# SDB628_Evaluation_board.net
KiCad netlist of a schematic drawn in EasyEDA Pro
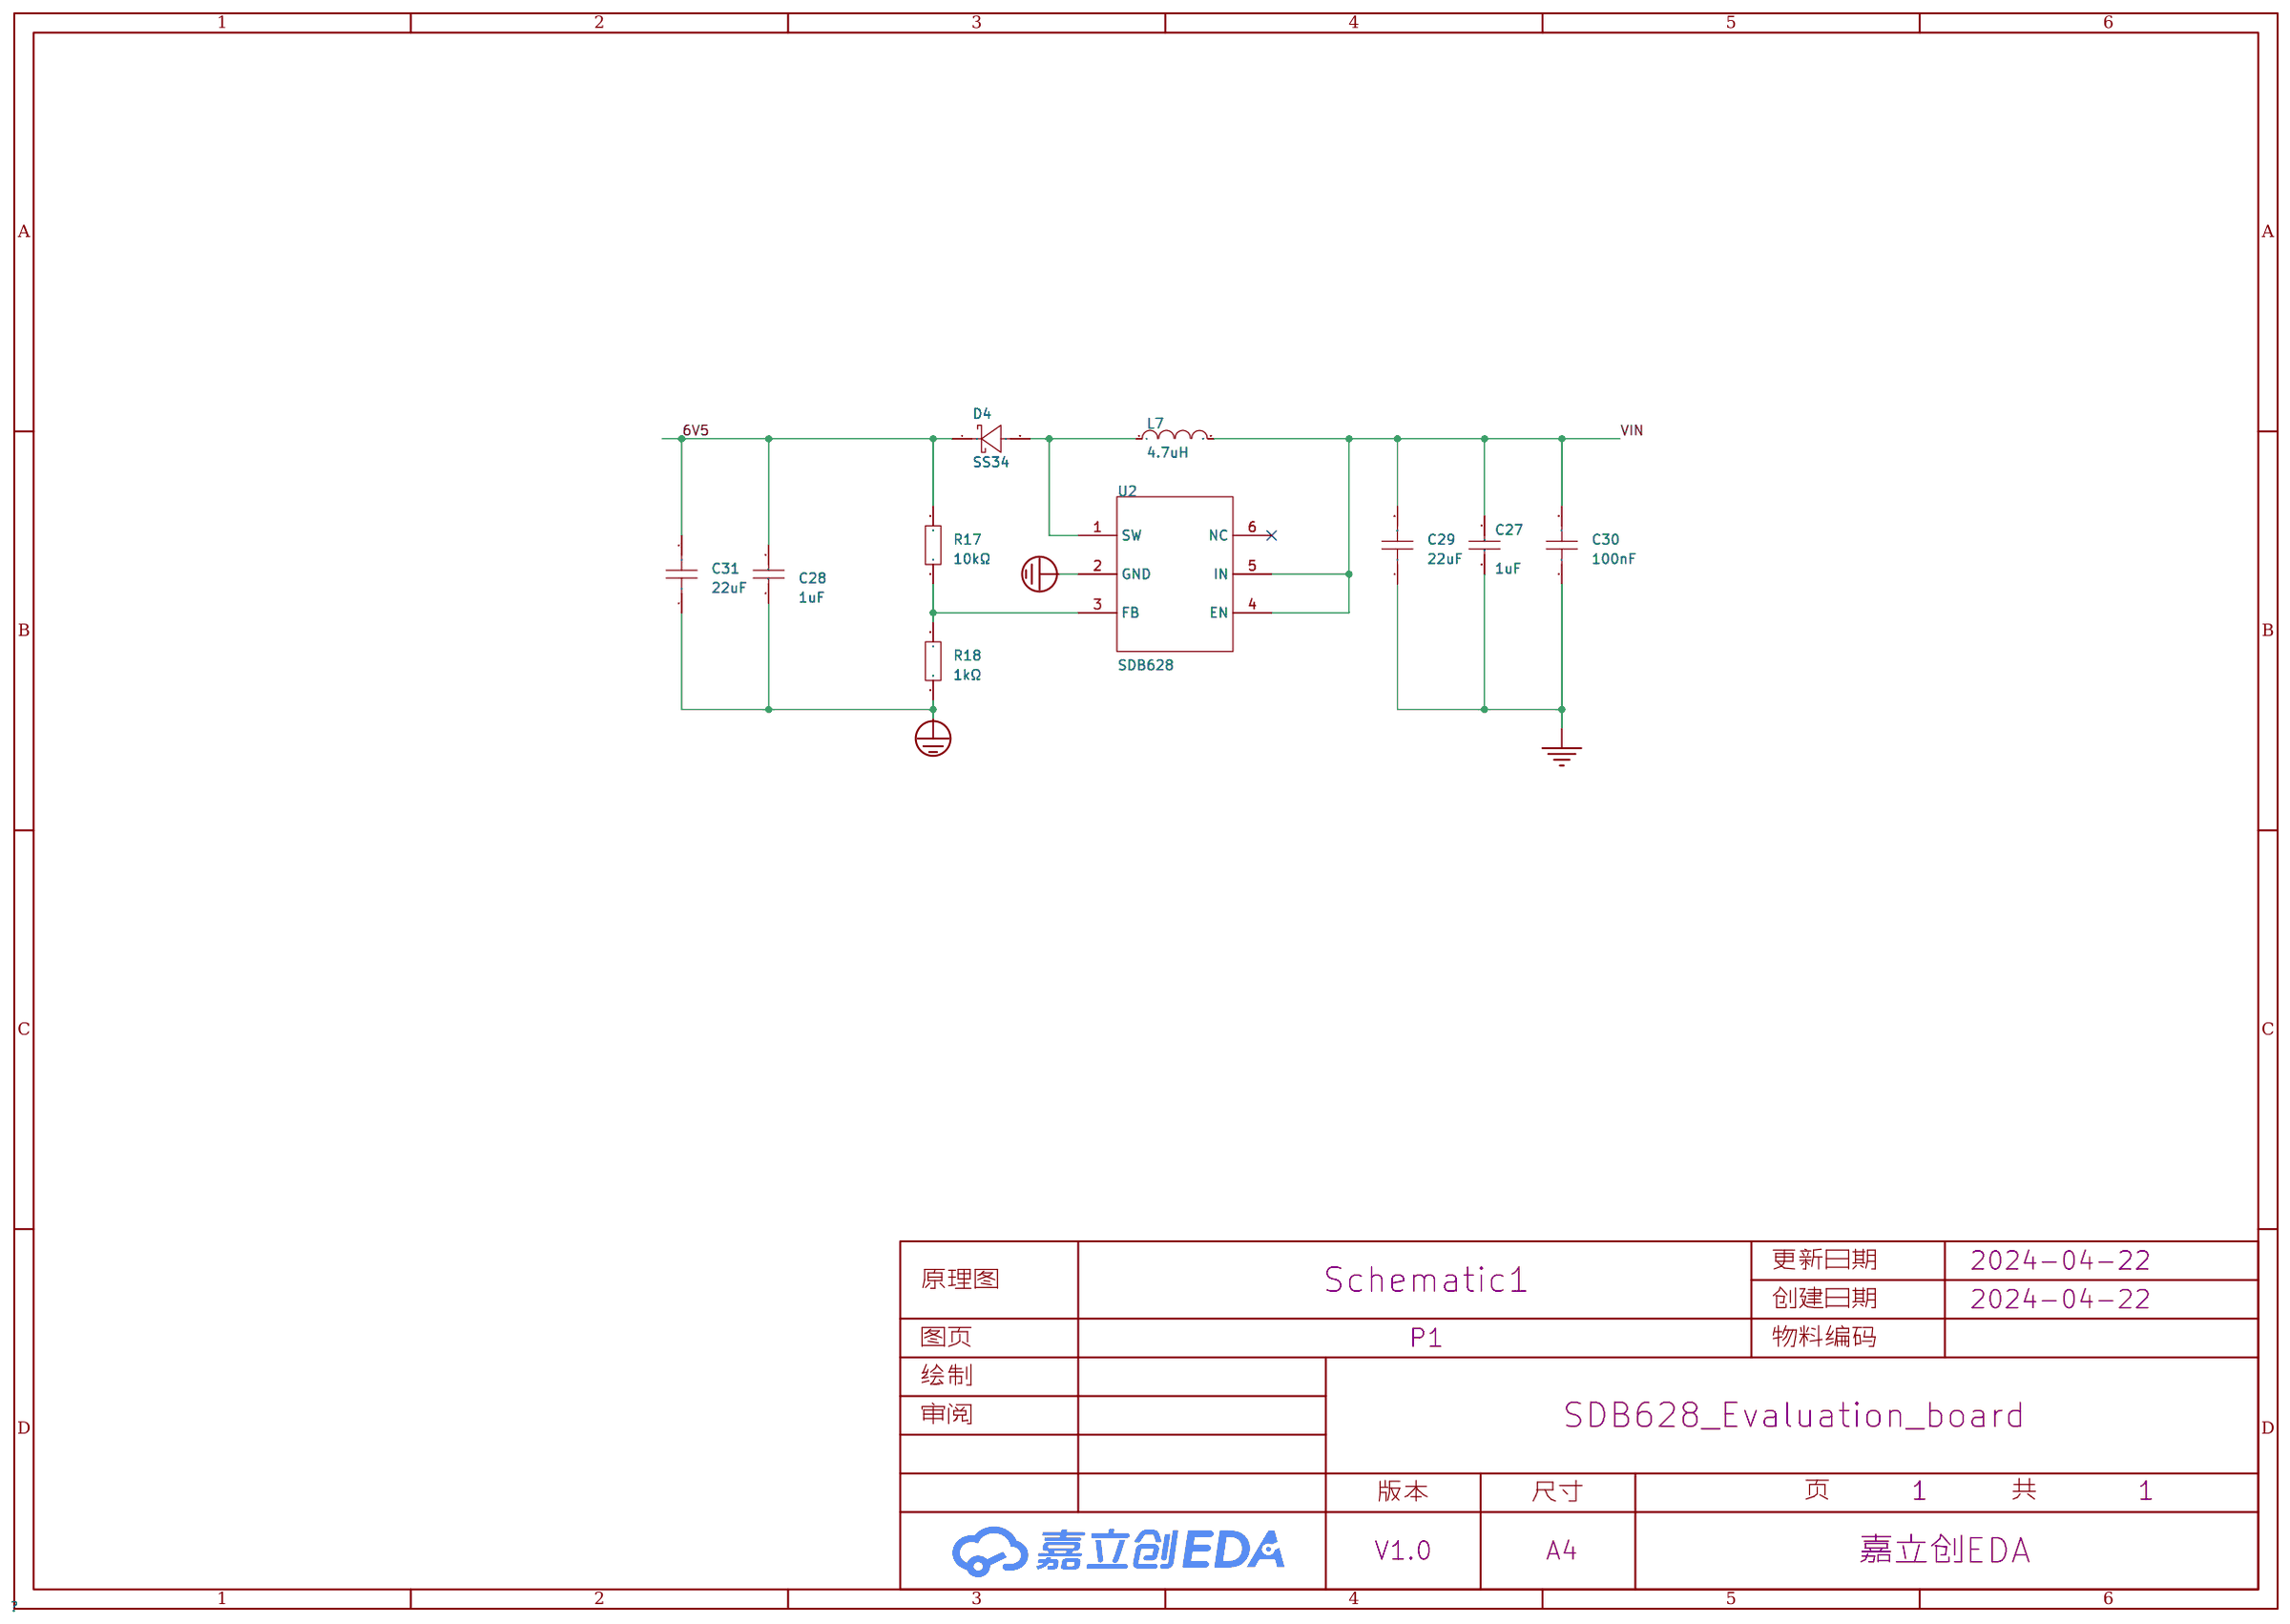
[diagram p0: schematic sheet]

(export (version "E")
  (design (tool "Eeschema 10.0.6"))
  (components
    (comp (ref "C27")
      (value "1uF")
      (footprint "easyedapro:C0603")
      (description "容值:1uF;精度:±10%;额定电压:50V;材质(温度系数):X5R;")
      (fields
        (field (name "Manufacturer Part") "CL10A105KB8NNNC")
        (field (name "Manufacturer") "SAMSUNG(三星)")
      )
      (libsource (lib "easyedapro") (part "CL10A105KB8NNNC"))
    )
    (comp (ref "C28")
      (value "1uF")
      (footprint "easyedapro:C0603")
      (description "容值:1uF;精度:±10%;额定电压:16V;材质(温度系数):X5R;")
      (fields
        (field (name "Manufacturer Part") "CL10A105KO8NNNC")
        (field (name "Manufacturer") "SAMSUNG(三星)")
      )
      (libsource (lib "easyedapro") (part "CL10A105KO8NNNC"))
    )
    (comp (ref "C29")
      (value "22uF")
      (footprint "easyedapro:c0805")
      (description "容值:22uF;精度:±20%;额定电压:25V;材质(温度系数):X5R;")
      (fields
        (field (name "Manufacturer Part") "CL21A226MAQNNNE")
        (field (name "Manufacturer") "SAMSUNG(三星)")
      )
      (libsource (lib "easyedapro") (part "CL21A226MAQNNNE"))
    )
    (comp (ref "C30")
      (value "100nF")
      (footprint "easyedapro:C0603")
      (description "容值:100nF;精度:±10%;额定电压:50V;材质(温度系数):X7R;")
      (fields
        (field (name "Manufacturer Part") "CC0603KRX7R9BB104")
        (field (name "Manufacturer") "YAGEO(国巨)")
      )
      (libsource (lib "easyedapro") (part "CC0603KRX7R9BB104"))
    )
    (comp (ref "C31")
      (value "22uF")
      (footprint "easyedapro:c0805")
      (description "容值:22uF;精度:±20%;额定电压:25V;材质(温度系数):X5R;")
      (fields
        (field (name "Manufacturer Part") "CL21A226MAQNNNE")
        (field (name "Manufacturer") "SAMSUNG(三星)")
      )
      (libsource (lib "easyedapro") (part "CL21A226MAQNNNE"))
    )
    (comp (ref "D4")
      (value "SS34")
      (footprint "easyedapro:SMA_L4.3-W2.5-LS5.0-RD")
      (description "二极管配置:独立式;正向压降(Vf):550mV@3A;直流反向耐压(Vr):40V;平均整流电流(Io):3A;")
      (fields (field (name "Manufacturer") "TWGMC(台湾迪嘉)"))
      (libsource (lib "easyedapro") (part "SS34_C727060"))
    )
    (comp (ref "L7")
      (value "4.7uH")
      (footprint "easyedapro:IND-SMD_L4.4-W4.2")
      (description "电感值:4.7uH;精度:±20%;额定电流:2.8A;饱和电流(Isat):3A;类型:一体成型电感;")
      (fields (field (name "Manufacturer Part") "FXL0420-4R7-M") (field (name "Manufacturer") "cjiang(长江微电)"))
      (libsource (lib "easyedapro") (part "FXL0420-4R7-M"))
    )
    (comp (ref "R17")
      (value "10kΩ")
      (footprint "easyedapro:R0603")
      (description "电阻类型:厚膜电阻;阻值:10kΩ;精度:±1%;功率:100mW;最大工作电压:75V;温度系数:±100ppm/°C;")
      (fields
        (field (name "Manufacturer Part") "0603WAF1002T5E")
        (field (name "Manufacturer") "UNI-ROYAL(厚声)")
      )
      (libsource (lib "easyedapro") (part "0603WAF1002T5E"))
    )
    (comp (ref "R18")
      (value "1kΩ")
      (footprint "easyedapro:R0603")
      (description "电阻类型:厚膜电阻;阻值:1kΩ;精度:±1%;功率:100mW;最大工作电压:75V;温度系数:±100ppm/°C;")
      (fields (field (name "Manufacturer Part") "RC0603FR-071KL") (field (name "Manufacturer") "YAGEO(国巨)"))
      (libsource (lib "easyedapro") (part "RC0603FR-071KL"))
    )
    (comp (ref "U2")
      (value "SDB628")
      (footprint "easyedapro:SOT-23-6_L2.9-W1.6-P0.95-LS2.8-BR")
      (description "功能类型:升压型;输入电压:2V~24V;输出电压:28V;输出电流(最大值):2A;")
      (fields (field (name "Manufacturer") "SHOUDING(首鼎半导体)"))
      (libsource (lib "easyedapro") (part "SDB628"))
    )
  )
  (nets
    (net (code "1") (name "/6V5") (class "Default")
      (node (ref "C28") (pin "1") (pinfunction "1_1") (pintype "input"))
      (node (ref "C31") (pin "2") (pinfunction "2_2") (pintype "unspecified"))
      (node (ref "D4") (pin "1") (pinfunction "C_1") (pintype "unspecified"))
      (node (ref "R17") (pin "2") (pinfunction "2_2") (pintype "input"))
    )
    (net (code "2") (name "/VIN") (class "Default")
      (node (ref "C27") (pin "2") (pinfunction "2_2") (pintype "input"))
      (node (ref "C29") (pin "2") (pinfunction "2_2") (pintype "unspecified"))
      (node (ref "C30") (pin "2") (pinfunction "2_2") (pintype "unspecified"))
      (node (ref "L7") (pin "2") (pinfunction "2_2") (pintype "unspecified"))
      (node (ref "U2") (pin "4") (pinfunction "EN_4") (pintype "input"))
      (node (ref "U2") (pin "5") (pinfunction "IN_5") (pintype "input"))
    )
    (net (code "3") (name "GND") (class "Default")
      (node (ref "C27") (pin "1") (pinfunction "1_1") (pintype "input"))
      (node (ref "C29") (pin "1") (pinfunction "1_1") (pintype "unspecified"))
      (node (ref "C30") (pin "1") (pinfunction "1_1") (pintype "unspecified"))
    )
    (net (code "4") (name "Net-(D4-A)") (class "Default")
      (node (ref "D4") (pin "2") (pinfunction "A_2") (pintype "unspecified"))
      (node (ref "L7") (pin "1") (pinfunction "1_1") (pintype "unspecified"))
      (node (ref "U2") (pin "1") (pinfunction "SW_1") (pintype "input"))
    )
    (net (code "5") (name "Net-(U2-FB)") (class "Default")
      (node (ref "R17") (pin "1") (pinfunction "1_1") (pintype "input"))
      (node (ref "R18") (pin "2") (pinfunction "2_2") (pintype "input"))
      (node (ref "U2") (pin "3") (pinfunction "FB_3") (pintype "input"))
    )
    (net (code "6") (name "PGND") (class "Default")
      (node (ref "C28") (pin "2") (pinfunction "2_2") (pintype "input"))
      (node (ref "C31") (pin "1") (pinfunction "1_1") (pintype "unspecified"))
      (node (ref "R18") (pin "1") (pinfunction "1_1") (pintype "input"))
      (node (ref "U2") (pin "2") (pinfunction "GND_2") (pintype "input"))
    )
    (net (code "7") (name "unconnected-(U2-NC-Pad6)") (class "Default")
      (node (ref "U2") (pin "6") (pinfunction "NC_6") (pintype "input+no_connect"))
    )
  )
)
